# PSU_VCC_CRUVI_ADJ_Buck.net
KiCad netlist of a schematic drawn in Altium Designer
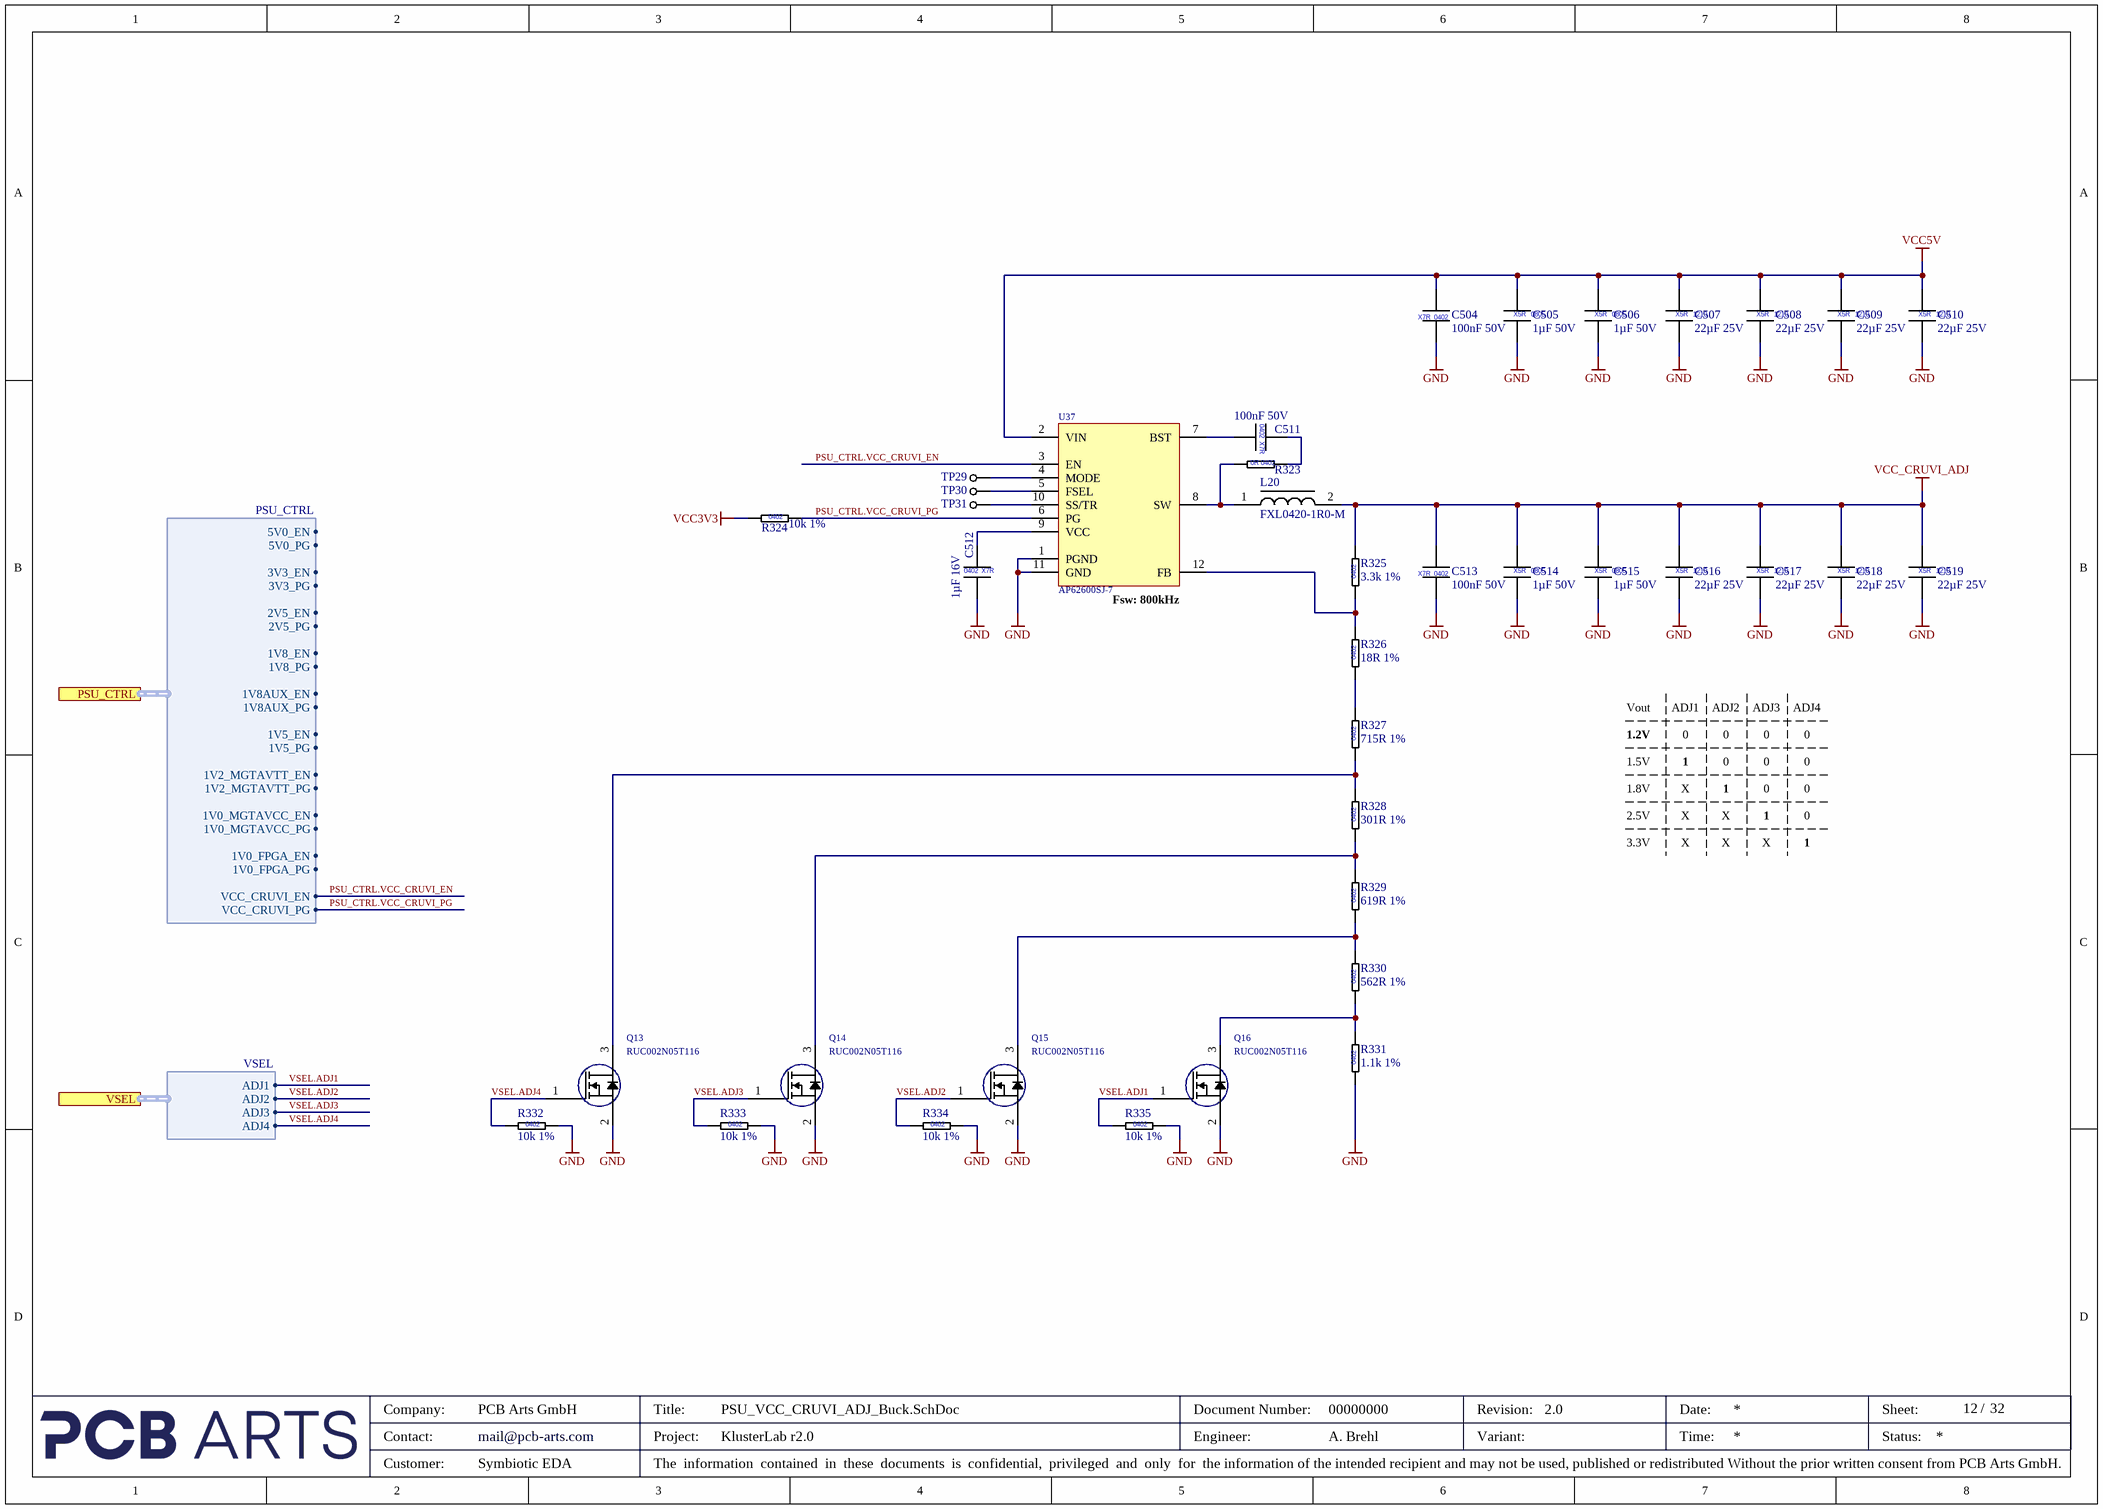
[diagram p0: PSU_VCC_CRUVI_ADJ_Buck.SchDoc]

(export (version "E")
  (design (tool "Eeschema 10.0.6"))
  (components
    (comp (ref "C504")
      (value "100nF 50V")
      (footprint "Cap:CAP_0402_L")
      (description "Multilayer Ceramic Capacitors MLCC - SMD/SMT 0402 50VDC")
      (libsource (lib "") (part "CAP_0402_100nF_50V_1"))
    )
    (comp (ref "C505")
      (value "1µF 50V")
      (footprint "Cap:CAP_0805")
      (description "Multilayer Ceramic Capacitors MLCC - SMD/SMT 0805 50VDC")
      (libsource (lib "Cap") (part "CAP_0805_1µF_50V"))
    )
    (comp (ref "C506")
      (value "1µF 50V")
      (footprint "Cap:CAP_0805")
      (description "Multilayer Ceramic Capacitors MLCC - SMD/SMT 0805 50VDC")
      (libsource (lib "Cap") (part "CAP_0805_1µF_50V"))
    )
    (comp (ref "C507")
      (value "22µF 25V")
      (footprint "Cap:CAP_1210")
      (description "Multilayer Ceramic Capacitors MLCC - SMD/SMT 1210 25VDC")
      (libsource (lib "Cap") (part "CAP_1210_22µF_25V"))
    )
    (comp (ref "C508")
      (value "22µF 25V")
      (footprint "Cap:CAP_1210")
      (description "Multilayer Ceramic Capacitors MLCC - SMD/SMT 1210 25VDC")
      (libsource (lib "Cap") (part "CAP_1210_22µF_25V"))
    )
    (comp (ref "C509")
      (value "22µF 25V")
      (footprint "Cap:CAP_1210")
      (description "Multilayer Ceramic Capacitors MLCC - SMD/SMT 1210 25VDC")
      (libsource (lib "Cap") (part "CAP_1210_22µF_25V"))
    )
    (comp (ref "C510")
      (value "22µF 25V")
      (footprint "Cap:CAP_1210")
      (description "Multilayer Ceramic Capacitors MLCC - SMD/SMT 1210 25VDC")
      (libsource (lib "Cap") (part "CAP_1210_22µF_25V"))
    )
    (comp (ref "C511")
      (value "100nF 50V")
      (footprint "Cap:CAP_0402_L")
      (description "Multilayer Ceramic Capacitors MLCC - SMD/SMT 0402 50VDC")
      (libsource (lib "Cap") (part "CAP_0402_100nF_50V"))
    )
    (comp (ref "C512")
      (value "1µF 16V")
      (footprint "Cap:CAP_0402_L")
      (description "Multilayer Ceramic Capacitors MLCC - SMD/SMT 0402 16VDC")
      (libsource (lib "Cap") (part "CAP_0402_1µF_16V"))
    )
    (comp (ref "C513")
      (value "100nF 50V")
      (footprint "Cap:CAP_0402_L")
      (description "Multilayer Ceramic Capacitors MLCC - SMD/SMT 0402 50VDC")
      (libsource (lib "") (part "CAP_0402_100nF_50V_1"))
    )
    (comp (ref "C514")
      (value "1µF 50V")
      (footprint "Cap:CAP_0805")
      (description "Multilayer Ceramic Capacitors MLCC - SMD/SMT 0805 50VDC")
      (libsource (lib "Cap") (part "CAP_0805_1µF_50V"))
    )
    (comp (ref "C515")
      (value "1µF 50V")
      (footprint "Cap:CAP_0805")
      (description "Multilayer Ceramic Capacitors MLCC - SMD/SMT 0805 50VDC")
      (libsource (lib "Cap") (part "CAP_0805_1µF_50V"))
    )
    (comp (ref "C516")
      (value "22µF 25V")
      (footprint "Cap:CAP_1210")
      (description "Multilayer Ceramic Capacitors MLCC - SMD/SMT 1210 25VDC")
      (libsource (lib "Cap") (part "CAP_1210_22µF_25V"))
    )
    (comp (ref "C517")
      (value "22µF 25V")
      (footprint "Cap:CAP_1210")
      (description "Multilayer Ceramic Capacitors MLCC - SMD/SMT 1210 25VDC")
      (libsource (lib "Cap") (part "CAP_1210_22µF_25V"))
    )
    (comp (ref "C518")
      (value "22µF 25V")
      (footprint "Cap:CAP_1210")
      (description "Multilayer Ceramic Capacitors MLCC - SMD/SMT 1210 25VDC")
      (libsource (lib "Cap") (part "CAP_1210_22µF_25V"))
    )
    (comp (ref "C519")
      (value "22µF 25V")
      (footprint "Cap:CAP_1210")
      (description "Multilayer Ceramic Capacitors MLCC - SMD/SMT 1210 25VDC")
      (libsource (lib "Cap") (part "CAP_1210_22µF_25V"))
    )
    (comp (ref "L20")
      (value "FXL0420-1R0-M")
      (footprint "Indc:FXL0420-1R0-M")
      (description "1uH ±20% 6A 27mΩ SMD,4.4x4.5x1.8mm Power Inductor")
      (libsource (lib "Indc") (part "1uH 6A 27mΩ  FXL0420-1R0-M"))
    )
    (comp (ref "Q13")
      (value "RUC002N05T116")
      (footprint "trans:SOT95P251X112-3N")
      (description "MOSFET N-Ch 1.2 VGS Spec")
      (libsource (lib "Trans") (part "RUC002N05T116_MOSFET N-Ch 1.2 VGS Spec"))
    )
    (comp (ref "Q14")
      (value "RUC002N05T116")
      (footprint "trans:SOT95P251X112-3N")
      (description "MOSFET N-Ch 1.2 VGS Spec")
      (libsource (lib "Trans") (part "RUC002N05T116_MOSFET N-Ch 1.2 VGS Spec"))
    )
    (comp (ref "Q15")
      (value "RUC002N05T116")
      (footprint "trans:SOT95P251X112-3N")
      (description "MOSFET N-Ch 1.2 VGS Spec")
      (libsource (lib "Trans") (part "RUC002N05T116_MOSFET N-Ch 1.2 VGS Spec"))
    )
    (comp (ref "Q16")
      (value "RUC002N05T116")
      (footprint "trans:SOT95P251X112-3N")
      (description "MOSFET N-Ch 1.2 VGS Spec")
      (libsource (lib "Trans") (part "RUC002N05T116_MOSFET N-Ch 1.2 VGS Spec"))
    )
    (comp (ref "R323")
      (value "0R Jumper")
      (footprint "Res:RES_0402_L")
      (description "Thick Film Resistors - SMD 0Ohm")
      (libsource (lib "Res") (part "RES_0402_0R Jumper"))
    )
    (comp (ref "R324")
      (value "10k 1%")
      (footprint "Res:RES_0402_L")
      (description "Thick Film Resistors - SMD 10kOhm 1%")
      (libsource (lib "Res") (part "RES_0402_10k_1%"))
    )
    (comp (ref "R325")
      (value "3.3k 1%")
      (footprint "Res:RES_0402_L")
      (description "Thick Film Resistors - SMD 3.3kOhm 1%")
      (libsource (lib "Res") (part "RES_0402_3.3k_1%"))
    )
    (comp (ref "R326")
      (value "18R 1%")
      (footprint "Res:RES_0402_L")
      (description "Thick Film Resistors - SMD 18Ohm 1%")
      (libsource (lib "Res") (part "RES_0402_18R_1%"))
    )
    (comp (ref "R327")
      (value "715R 1%")
      (footprint "Res:RES_0402_L")
      (description "Thick Film Resistors - SMD 715Ohm 1%")
      (libsource (lib "Res") (part "RES_0402_715R_1%"))
    )
    (comp (ref "R328")
      (value "301R 1%")
      (footprint "Res:RES_0402_L")
      (description "Thick Film Resistors - SMD 301Ohm 1%")
      (libsource (lib "Res") (part "RES_0402_301R_1%"))
    )
    (comp (ref "R329")
      (value "619R 1%")
      (footprint "Res:RES_0402_L")
      (description "Thick Film Resistors - SMD 619Ohm 1%")
      (libsource (lib "Res") (part "RES_0402_619R_1%"))
    )
    (comp (ref "R330")
      (value "562R 1%")
      (footprint "Res:RES_0402_L")
      (description "Thick Film Resistors - SMD 562Ohm 1%")
      (libsource (lib "Res") (part "RES_0402_562R_1%"))
    )
    (comp (ref "R331")
      (value "1.1k 1%")
      (footprint "Res:RES_0402_L")
      (description "Thick Film Resistors - SMD 1.1kOhm 1%")
      (libsource (lib "Res") (part "RES_0402_1.1k_1%"))
    )
    (comp (ref "R332")
      (value "10k 1%")
      (footprint "Res:RES_0402_L")
      (description "Thick Film Resistors - SMD 10kOhm 1%")
      (libsource (lib "Res") (part "RES_0402_10k_1%"))
    )
    (comp (ref "R333")
      (value "10k 1%")
      (footprint "Res:RES_0402_L")
      (description "Thick Film Resistors - SMD 10kOhm 1%")
      (libsource (lib "Res") (part "RES_0402_10k_1%"))
    )
    (comp (ref "R334")
      (value "10k 1%")
      (footprint "Res:RES_0402_L")
      (description "Thick Film Resistors - SMD 10kOhm 1%")
      (libsource (lib "Res") (part "RES_0402_10k_1%"))
    )
    (comp (ref "R335")
      (value "10k 1%")
      (footprint "Res:RES_0402_L")
      (description "Thick Film Resistors - SMD 10kOhm 1%")
      (libsource (lib "Res") (part "RES_0402_10k_1%"))
    )
    (comp (ref "TP29")
      (value "Testpoint")
      (footprint "Electro_mech:Testpoint 0.8mm")
      (description "Testpoint 0.8mm")
      (libsource (lib "Electro_Mech") (part "Testpoint 0.8mm"))
    )
    (comp (ref "TP30")
      (value "Testpoint")
      (footprint "Electro_mech:Testpoint 0.8mm")
      (description "Testpoint 0.8mm")
      (libsource (lib "Electro_Mech") (part "Testpoint 0.8mm"))
    )
    (comp (ref "TP31")
      (value "Testpoint")
      (footprint "Electro_mech:Testpoint 0.8mm")
      (description "Testpoint 0.8mm")
      (libsource (lib "Electro_Mech") (part "Testpoint 0.8mm"))
    )
    (comp (ref "U37")
      (value "AP62600SJ-7")
      (footprint "Power:QFN50P200x300x85-12")
      (description "4.5V TO 18V INPUT, 6A SYNCHRONOUS BUCK CONVERTER")
      (libsource (lib "Power") (part "AP62600SJ-7_4.5V TO 18V INPUT, 6A SYNCHRONOUS BUCK CONVERTER"))
    )
  )
  (nets
    (net (code "3") (name "/PSU_CTRL.VCC_CRUVI_EN") (class "Default")
      (node (ref "U37") (pin "3") (pinfunction "EN_3") (pintype "passive"))
    )
    (net (code "4") (name "/PSU_CTRL.VCC_CRUVI_PG") (class "Default")
      (node (ref "R324") (pin "2") (pinfunction "2_2") (pintype "passive"))
      (node (ref "U37") (pin "6") (pinfunction "PG_6") (pintype "passive"))
    )
    (net (code "5") (name "/VSEL.ADJ1") (class "Default")
      (node (ref "Q16") (pin "1") (pinfunction "G_1") (pintype "passive"))
      (node (ref "R335") (pin "1") (pinfunction "1_1") (pintype "passive"))
    )
    (net (code "6") (name "/VSEL.ADJ2") (class "Default")
      (node (ref "Q15") (pin "1") (pinfunction "G_1") (pintype "passive"))
      (node (ref "R334") (pin "1") (pinfunction "1_1") (pintype "passive"))
    )
    (net (code "7") (name "/VSEL.ADJ3") (class "Default")
      (node (ref "Q14") (pin "1") (pinfunction "G_1") (pintype "passive"))
      (node (ref "R333") (pin "1") (pinfunction "1_1") (pintype "passive"))
    )
    (net (code "8") (name "/VSEL.ADJ4") (class "Default")
      (node (ref "Q13") (pin "1") (pinfunction "G_1") (pintype "passive"))
      (node (ref "R332") (pin "1") (pinfunction "1_1") (pintype "passive"))
    )
    (net (code "11") (name "GND") (class "Default")
      (node (ref "C504") (pin "1") (pinfunction "1_1") (pintype "passive"))
      (node (ref "C505") (pin "2") (pinfunction "2_2") (pintype "passive"))
      (node (ref "C506") (pin "2") (pinfunction "2_2") (pintype "passive"))
      (node (ref "C507") (pin "2") (pinfunction "2_2") (pintype "passive"))
      (node (ref "C508") (pin "2") (pinfunction "2_2") (pintype "passive"))
      (node (ref "C509") (pin "2") (pinfunction "2_2") (pintype "passive"))
      (node (ref "C510") (pin "2") (pinfunction "2_2") (pintype "passive"))
      (node (ref "C512") (pin "2") (pinfunction "2_2") (pintype "passive"))
      (node (ref "C513") (pin "1") (pinfunction "1_1") (pintype "passive"))
      (node (ref "C514") (pin "2") (pinfunction "2_2") (pintype "passive"))
      (node (ref "C515") (pin "2") (pinfunction "2_2") (pintype "passive"))
      (node (ref "C516") (pin "2") (pinfunction "2_2") (pintype "passive"))
      (node (ref "C517") (pin "2") (pinfunction "2_2") (pintype "passive"))
      (node (ref "C518") (pin "2") (pinfunction "2_2") (pintype "passive"))
      (node (ref "C519") (pin "2") (pinfunction "2_2") (pintype "passive"))
      (node (ref "Q13") (pin "2") (pinfunction "D_2") (pintype "passive"))
      (node (ref "Q14") (pin "2") (pinfunction "D_2") (pintype "passive"))
      (node (ref "Q15") (pin "2") (pinfunction "D_2") (pintype "passive"))
      (node (ref "Q16") (pin "2") (pinfunction "D_2") (pintype "passive"))
      (node (ref "R331") (pin "1") (pinfunction "1_1") (pintype "passive"))
      (node (ref "R332") (pin "2") (pinfunction "2_2") (pintype "passive"))
      (node (ref "R333") (pin "2") (pinfunction "2_2") (pintype "passive"))
      (node (ref "R334") (pin "2") (pinfunction "2_2") (pintype "passive"))
      (node (ref "R335") (pin "2") (pinfunction "2_2") (pintype "passive"))
      (node (ref "U37") (pin "1") (pinfunction "PGND_1") (pintype "passive"))
      (node (ref "U37") (pin "11") (pinfunction "GND_11") (pintype "passive"))
    )
    (net (code "12") (name "Net-(C511-Pad1)") (class "Default")
      (node (ref "C511") (pin "1") (pinfunction "1_1") (pintype "passive"))
      (node (ref "R323") (pin "2") (pinfunction "2_2") (pintype "passive"))
    )
    (net (code "13") (name "Net-(Q13-S)") (class "Default")
      (node (ref "Q13") (pin "3") (pinfunction "S_3") (pintype "passive"))
      (node (ref "R327") (pin "1") (pinfunction "1_1") (pintype "passive"))
      (node (ref "R328") (pin "2") (pinfunction "2_2") (pintype "passive"))
    )
    (net (code "14") (name "Net-(Q14-S)") (class "Default")
      (node (ref "Q14") (pin "3") (pinfunction "S_3") (pintype "passive"))
      (node (ref "R328") (pin "1") (pinfunction "1_1") (pintype "passive"))
      (node (ref "R329") (pin "2") (pinfunction "2_2") (pintype "passive"))
    )
    (net (code "15") (name "Net-(Q15-S)") (class "Default")
      (node (ref "Q15") (pin "3") (pinfunction "S_3") (pintype "passive"))
      (node (ref "R329") (pin "1") (pinfunction "1_1") (pintype "passive"))
      (node (ref "R330") (pin "2") (pinfunction "2_2") (pintype "passive"))
    )
    (net (code "16") (name "Net-(Q16-S)") (class "Default")
      (node (ref "Q16") (pin "3") (pinfunction "S_3") (pintype "passive"))
      (node (ref "R330") (pin "1") (pinfunction "1_1") (pintype "passive"))
      (node (ref "R331") (pin "2") (pinfunction "2_2") (pintype "passive"))
    )
    (net (code "17") (name "Net-(R326-Pad1)") (class "Default")
      (node (ref "R326") (pin "1") (pinfunction "1_1") (pintype "passive"))
      (node (ref "R327") (pin "2") (pinfunction "2_2") (pintype "passive"))
    )
    (net (code "18") (name "Net-(TP29-GND)") (class "Default")
      (node (ref "TP29") (pin "1") (pinfunction "GND_1") (pintype "passive"))
      (node (ref "U37") (pin "4") (pinfunction "MODE_4") (pintype "passive"))
    )
    (net (code "19") (name "Net-(TP30-GND)") (class "Default")
      (node (ref "TP30") (pin "1") (pinfunction "GND_1") (pintype "passive"))
      (node (ref "U37") (pin "5") (pinfunction "FSEL_5") (pintype "passive"))
    )
    (net (code "20") (name "Net-(TP31-GND)") (class "Default")
      (node (ref "TP31") (pin "1") (pinfunction "GND_1") (pintype "passive"))
      (node (ref "U37") (pin "10") (pinfunction "SS/TR_10") (pintype "passive"))
    )
    (net (code "21") (name "Net-(U37-BST)") (class "Default")
      (node (ref "C511") (pin "2") (pinfunction "2_2") (pintype "passive"))
      (node (ref "U37") (pin "7") (pinfunction "BST_7") (pintype "passive"))
    )
    (net (code "22") (name "Net-(U37-FB)") (class "Default")
      (node (ref "R325") (pin "1") (pinfunction "1_1") (pintype "passive"))
      (node (ref "R326") (pin "2") (pinfunction "2_2") (pintype "passive"))
      (node (ref "U37") (pin "12") (pinfunction "FB_12") (pintype "passive"))
    )
    (net (code "23") (name "Net-(U37-SW)") (class "Default")
      (node (ref "L20") (pin "1") (pinfunction "1_1") (pintype "passive"))
      (node (ref "R323") (pin "1") (pinfunction "1_1") (pintype "passive"))
      (node (ref "U37") (pin "8") (pinfunction "SW_8") (pintype "passive"))
    )
    (net (code "24") (name "Net-(U37-VCC)") (class "Default")
      (node (ref "C512") (pin "1") (pinfunction "1_1") (pintype "passive"))
      (node (ref "U37") (pin "9") (pinfunction "VCC_9") (pintype "passive"))
    )
    (net (code "25") (name "VCC3V3") (class "Default")
      (node (ref "R324") (pin "1") (pinfunction "1_1") (pintype "passive"))
    )
    (net (code "26") (name "VCC5V") (class "Default")
      (node (ref "C504") (pin "2") (pinfunction "2_2") (pintype "passive"))
      (node (ref "C505") (pin "1") (pinfunction "1_1") (pintype "passive"))
      (node (ref "C506") (pin "1") (pinfunction "1_1") (pintype "passive"))
      (node (ref "C507") (pin "1") (pinfunction "1_1") (pintype "passive"))
      (node (ref "C508") (pin "1") (pinfunction "1_1") (pintype "passive"))
      (node (ref "C509") (pin "1") (pinfunction "1_1") (pintype "passive"))
      (node (ref "C510") (pin "1") (pinfunction "1_1") (pintype "passive"))
      (node (ref "U37") (pin "2") (pinfunction "VIN_2") (pintype "passive"))
    )
    (net (code "27") (name "VCC_CRUVI_ADJ") (class "Default")
      (node (ref "C513") (pin "2") (pinfunction "2_2") (pintype "passive"))
      (node (ref "C514") (pin "1") (pinfunction "1_1") (pintype "passive"))
      (node (ref "C515") (pin "1") (pinfunction "1_1") (pintype "passive"))
      (node (ref "C516") (pin "1") (pinfunction "1_1") (pintype "passive"))
      (node (ref "C517") (pin "1") (pinfunction "1_1") (pintype "passive"))
      (node (ref "C518") (pin "1") (pinfunction "1_1") (pintype "passive"))
      (node (ref "C519") (pin "1") (pinfunction "1_1") (pintype "passive"))
      (node (ref "L20") (pin "2") (pinfunction "2_2") (pintype "passive"))
      (node (ref "R325") (pin "2") (pinfunction "2_2") (pintype "passive"))
    )
  )
)
